# LowPassFilter.net
KiCad netlist of a schematic drawn in Altium Designer
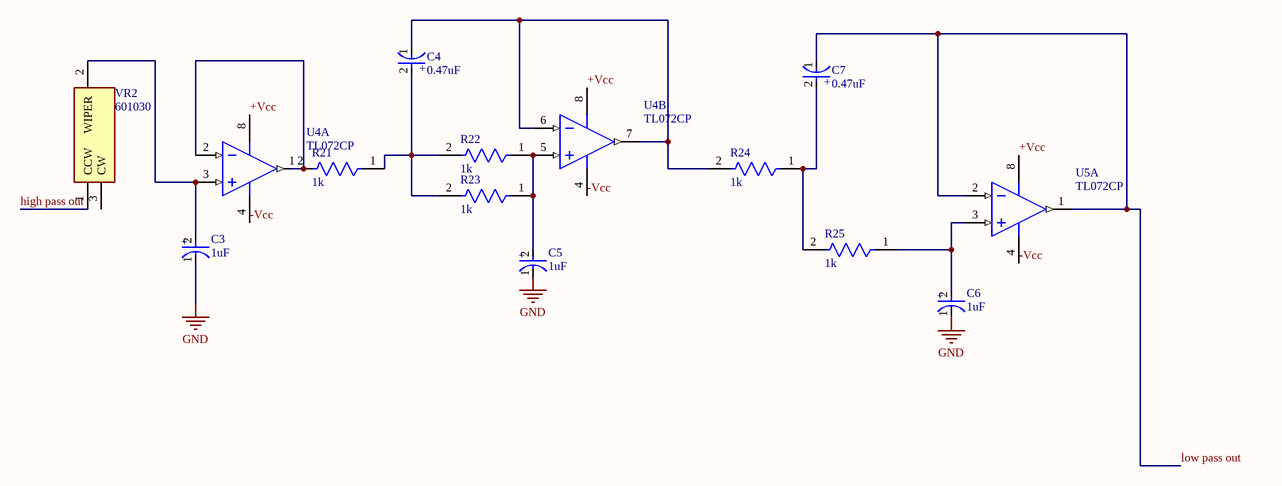
[diagram p0: LowPassFilter.SchDoc]

(export (version "E")
  (design (tool "Eeschema 10.0.6"))
  (components
    (comp (ref "C3")
      (value "1uF")
      (footprint "FP-TAP105K035SCS-MFG")
      (description "CAP TANT 1UF 10% 35V RADIAL")
      (fields (field (name "VOLTAGE") "20V") (field (name "TOLERANCE") "10%"))
      (libsource (lib "Altium Content Vault") (part "a00bbbee19879c290e62620ae7e47b1"))
    )
    (comp (ref "C4")
      (value "0.47uF")
      (footprint "FP-RAD-TH-D_5_0_5-L_11_1-MFG")
      (description "Aluminum Electrolytic Capacitors (Radial Lead Type) 0.47uF ±20% 63V")
      (fields (field (name "TOLERANCE") "20%") (field (name "VOLTAGE") "63V"))
      (libsource (lib "Altium Content Vault") (part "a00bbbee19879c290e62620ae7e47b1"))
    )
    (comp (ref "C5")
      (value "1uF")
      (footprint "FP-TAP105K035SCS-MFG")
      (description "CAP TANT 1UF 10% 35V RADIAL")
      (fields (field (name "VOLTAGE") "20V") (field (name "TOLERANCE") "10%"))
      (libsource (lib "Altium Content Vault") (part "a00bbbee19879c290e62620ae7e47b1"))
    )
    (comp (ref "C6")
      (value "1uF")
      (footprint "FP-TAP105K035SCS-MFG")
      (description "CAP TANT 1UF 10% 35V RADIAL")
      (fields (field (name "VOLTAGE") "20V") (field (name "TOLERANCE") "10%"))
      (libsource (lib "Altium Content Vault") (part "a00bbbee19879c290e62620ae7e47b1"))
    )
    (comp (ref "C7")
      (value "0.47uF")
      (footprint "FP-RAD-TH-D_5_0_5-L_11_1-MFG")
      (description "Aluminum Electrolytic Capacitors (Radial Lead Type) 0.47uF ±20% 63V")
      (fields (field (name "TOLERANCE") "20%") (field (name "VOLTAGE") "63V"))
      (libsource (lib "Altium Content Vault") (part "a00bbbee19879c290e62620ae7e47b1"))
    )
    (comp (ref "R21")
      (value "1k")
      (footprint "FP-CFR-25-MFG")
      (description "RES 10 OHM 1/4W 5% AXIAL")
      (fields (field (name "TOLERANCE") "5%"))
      (libsource (lib "Altium Content Vault") (part "1029c3af85768c4190bb7ad29bc67b5"))
    )
    (comp (ref "R22")
      (value "1k")
      (footprint "FP-CFR-25-MFG")
      (description "RES 10 OHM 1/4W 5% AXIAL")
      (fields (field (name "TOLERANCE") "5%"))
      (libsource (lib "Altium Content Vault") (part "1029c3af85768c4190bb7ad29bc67b5"))
    )
    (comp (ref "R23")
      (value "1k")
      (footprint "FP-CFR-25-MFG")
      (description "RES 10 OHM 1/4W 5% AXIAL")
      (fields (field (name "TOLERANCE") "5%"))
      (libsource (lib "Altium Content Vault") (part "1029c3af85768c4190bb7ad29bc67b5"))
    )
    (comp (ref "R24")
      (value "1k")
      (footprint "FP-CFR-25-MFG")
      (description "RES 10 OHM 1/4W 5% AXIAL")
      (fields (field (name "TOLERANCE") "5%"))
      (libsource (lib "Altium Content Vault") (part "1029c3af85768c4190bb7ad29bc67b5"))
    )
    (comp (ref "R25")
      (value "1k")
      (footprint "FP-CFR-25-MFG")
      (description "RES 10 OHM 1/4W 5% AXIAL")
      (fields (field (name "TOLERANCE") "5%"))
      (libsource (lib "Altium Content Vault") (part "1029c3af85768c4190bb7ad29bc67b5"))
    )
    (comp (ref "U4")
      (value "TL072CP")
      (footprint "P0008A")
      (fields (field (name "MANUFACTURER") "Texas Instruments"))
      (libsource (lib "Altium Content Vault") (part "TI-AMP-D6-2-8_D"))
    )
    (comp (ref "U5")
      (value "TL072CP")
      (footprint "P0008A")
      (fields (field (name "MANUFACTURER") "Texas Instruments"))
      (libsource (lib "Altium Content Vault") (part "TI-AMP-D6-2-8_D"))
    )
    (comp (ref "VR2")
      (value "601030")
      (footprint "SamacSys:601030")
      (description "Variable Resistor")
      (fields (field (name "MOUSER PART NUMBER") "581-601030"))
      (libsource (lib "*") (part "601030"))
    )
  )
  (nets
    (net (code "1") (name "/+Vcc") (class "Default")
      (node (ref "U4") (pin "8") (pinfunction "VCC+_8") (pintype "power_in"))
      (node (ref "U5") (pin "8") (pinfunction "VCC+_8") (pintype "power_in"))
    )
    (net (code "2") (name "/-Vcc") (class "Default")
      (node (ref "U4") (pin "4") (pinfunction "VCC-_4") (pintype "power_in"))
      (node (ref "U5") (pin "4") (pinfunction "VCC-_4") (pintype "power_in"))
    )
    (net (code "3") (name "/high pass out") (class "Default")
      (node (ref "VR2") (pin "1") (pinfunction "CCW_1") (pintype "passive"))
    )
    (net (code "4") (name "/low pass out") (class "Default")
      (node (ref "C7") (pin "1") (pinfunction "C_1") (pintype "passive"))
      (node (ref "U5") (pin "1") (pinfunction "OUT1_1") (pintype "output"))
      (node (ref "U5") (pin "2") (pinfunction "IN1-_2") (pintype "input"))
    )
    (net (code "5") (name "GND") (class "Default")
      (node (ref "C3") (pin "1") (pinfunction "C_1") (pintype "passive"))
      (node (ref "C5") (pin "1") (pinfunction "C_1") (pintype "passive"))
      (node (ref "C6") (pin "1") (pinfunction "C_1") (pintype "passive"))
    )
    (net (code "6") (name "Net-(C3-A)") (class "Default")
      (node (ref "C3") (pin "2") (pinfunction "A_2") (pintype "passive"))
      (node (ref "U4") (pin "3") (pinfunction "IN1+_3") (pintype "input"))
      (node (ref "VR2") (pin "2") (pinfunction "WIPER_2") (pintype "passive"))
    )
    (net (code "7") (name "Net-(C4-A)") (class "Default")
      (node (ref "C4") (pin "2") (pinfunction "A_2") (pintype "passive"))
      (node (ref "R21") (pin "1") (pinfunction "1_1") (pintype "passive"))
      (node (ref "R22") (pin "2") (pinfunction "2_2") (pintype "passive"))
      (node (ref "R23") (pin "2") (pinfunction "2_2") (pintype "passive"))
    )
    (net (code "8") (name "Net-(C4-C)") (class "Default")
      (node (ref "C4") (pin "1") (pinfunction "C_1") (pintype "passive"))
      (node (ref "R24") (pin "2") (pinfunction "2_2") (pintype "passive"))
      (node (ref "U4") (pin "6") (pinfunction "IN2-_6") (pintype "input"))
      (node (ref "U4") (pin "7") (pinfunction "OUT2_7") (pintype "output"))
    )
    (net (code "9") (name "Net-(C5-A)") (class "Default")
      (node (ref "C5") (pin "2") (pinfunction "A_2") (pintype "passive"))
      (node (ref "R22") (pin "1") (pinfunction "1_1") (pintype "passive"))
      (node (ref "R23") (pin "1") (pinfunction "1_1") (pintype "passive"))
      (node (ref "U4") (pin "5") (pinfunction "IN2+_5") (pintype "input"))
    )
    (net (code "10") (name "Net-(C6-A)") (class "Default")
      (node (ref "C6") (pin "2") (pinfunction "A_2") (pintype "passive"))
      (node (ref "R25") (pin "1") (pinfunction "1_1") (pintype "passive"))
      (node (ref "U5") (pin "3") (pinfunction "IN1+_3") (pintype "input"))
    )
    (net (code "11") (name "Net-(C7-A)") (class "Default")
      (node (ref "C7") (pin "2") (pinfunction "A_2") (pintype "passive"))
      (node (ref "R24") (pin "1") (pinfunction "1_1") (pintype "passive"))
      (node (ref "R25") (pin "2") (pinfunction "2_2") (pintype "passive"))
    )
    (net (code "12") (name "Net-(U4A-IN1-)") (class "Default")
      (node (ref "R21") (pin "2") (pinfunction "2_2") (pintype "passive"))
      (node (ref "U4") (pin "1") (pinfunction "OUT1_1") (pintype "output"))
      (node (ref "U4") (pin "2") (pinfunction "IN1-_2") (pintype "input"))
    )
    (net (code "13") (name "unconnected-(VR2-CW-Pad3)") (class "Default")
      (node (ref "VR2") (pin "3") (pinfunction "CW_3") (pintype "passive"))
    )
  )
)
